# EXS82_USB.net
KiCad netlist of a schematic drawn in Altium Designer
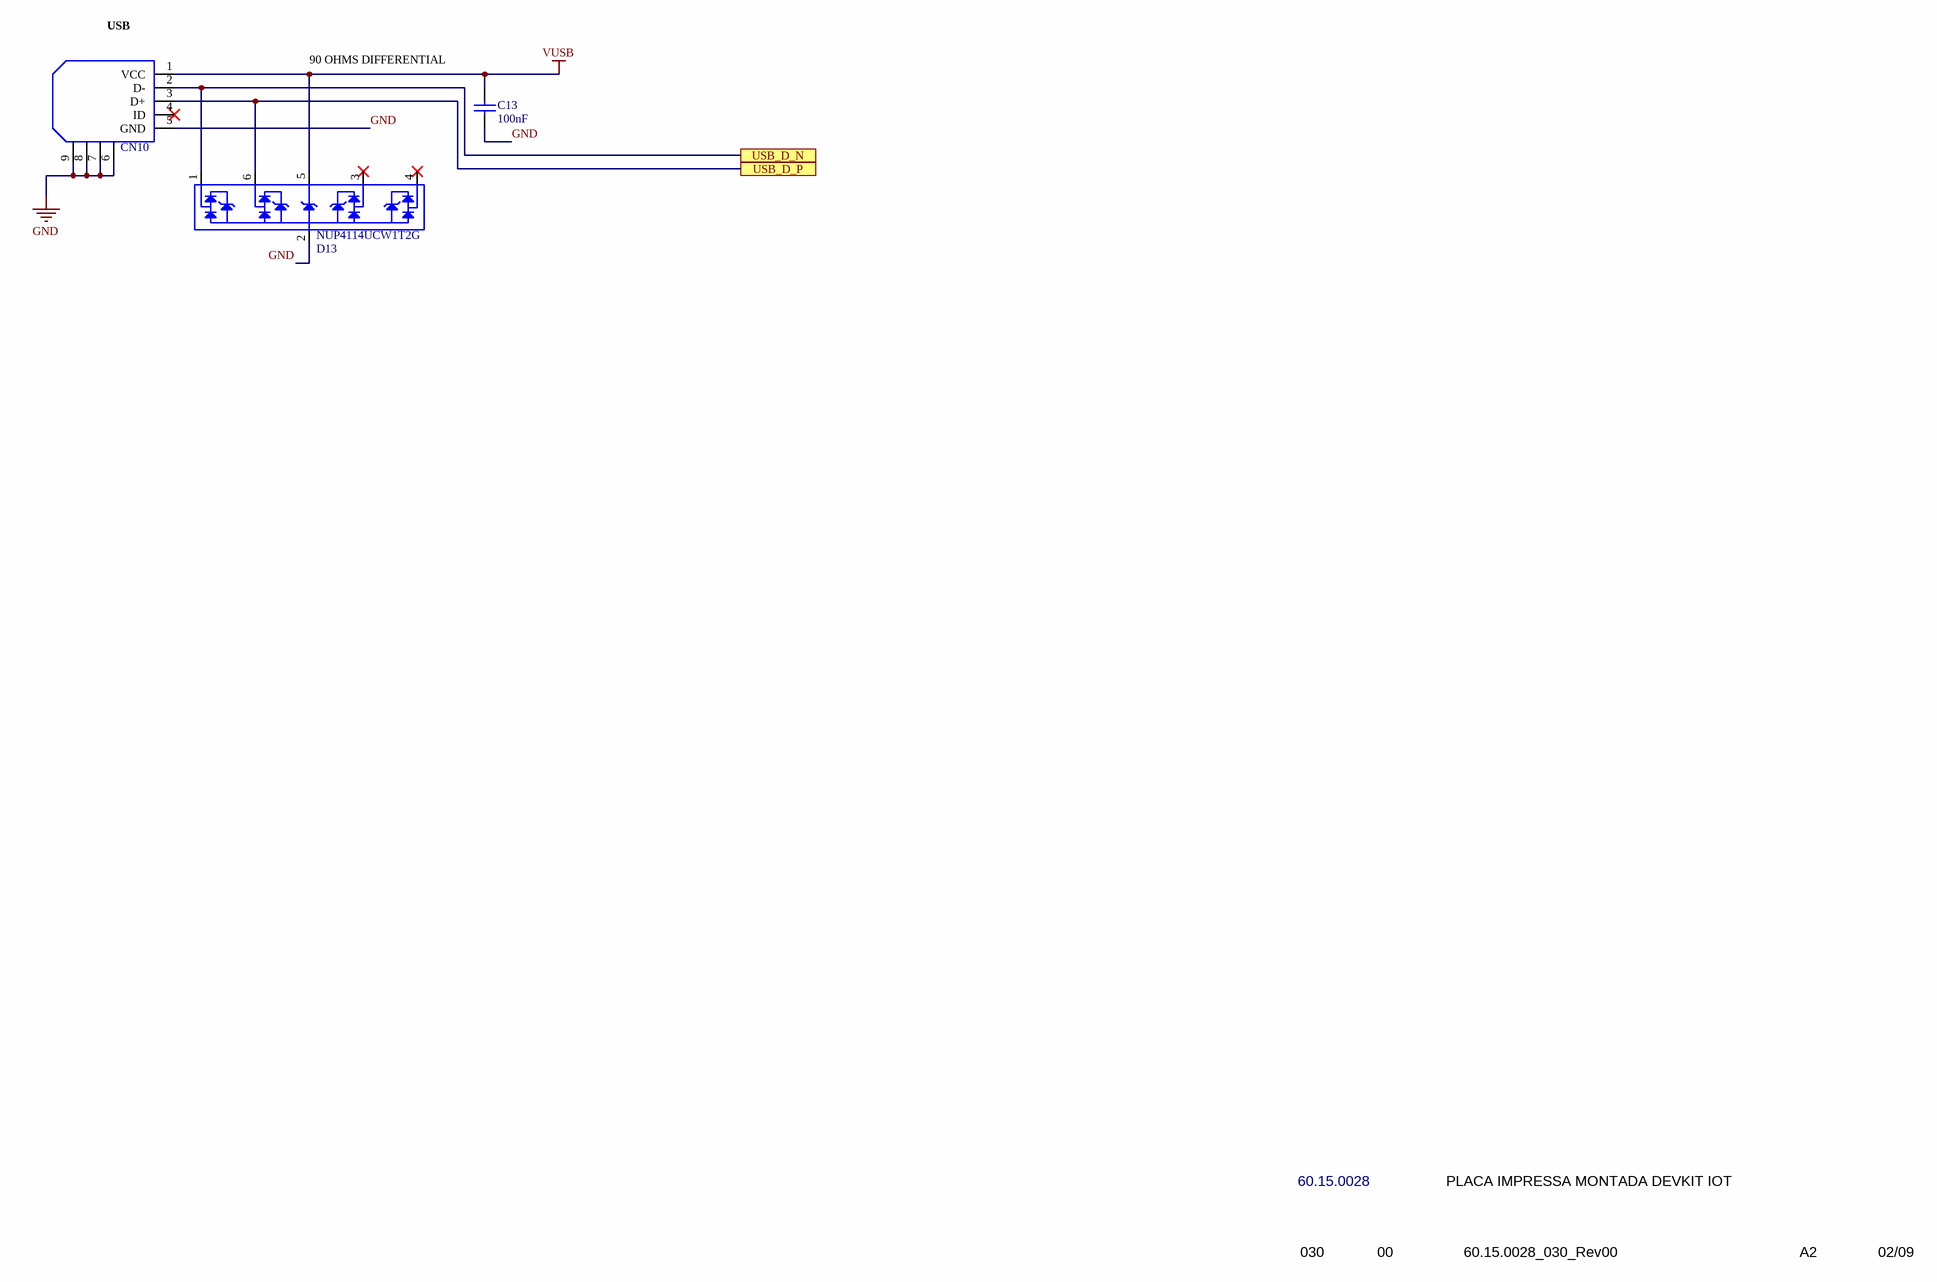
[diagram p0: EXS82_USB.SchDoc]

(export (version "E")
  (design (tool "Eeschema 10.0.6"))
  (components
    (comp (ref "C13")
      (value "16.23.0803")
      (footprint "16.23.0803")
      (description "CAPACITOR CERAMICO 100nF 16V 10%% X5R SMD 0201")
      (fields (field (name "ALTIUM_UNNAMED_1") "100nF"))
      (libsource (lib "OMNI-CAPACITORES") (part "16.23.0803"))
    )
    (comp (ref "CN10")
      (value "28.14.0512")
      (footprint "28.14.0512")
      (description "CONN USB MICRO B RECPT SMT R/A")
      (libsource (lib "OMNI-CONECTORES") (part "28.14.0512"))
    )
    (comp (ref "D13")
      (value "32.27.0043")
      (footprint "32.27.0043")
      (description "DIODO SUPRESSOR 5.5V 10V SC88")
      (fields (field (name "ALTIUM_UNNAMED_1") "NUP4114UCW1T2G"))
      (libsource (lib "OMNI-DIODOS_LED´s_DISPLAYS") (part "32.27.0043"))
    )
  )
  (nets
    (net (code "1") (name "/USB_D_N") (class "Default")
      (node (ref "CN10") (pin "2") (pinfunction "D-_2") (pintype "passive"))
      (node (ref "D13") (pin "1") (pinfunction "1_1") (pintype "passive"))
    )
    (net (code "2") (name "/USB_D_P") (class "Default")
      (node (ref "CN10") (pin "3") (pinfunction "D+_3") (pintype "passive"))
      (node (ref "D13") (pin "6") (pinfunction "6_6") (pintype "passive"))
    )
    (net (code "3") (name "GND") (class "Default")
      (node (ref "C13") (pin "1") (pinfunction "1_1") (pintype "passive"))
      (node (ref "CN10") (pin "5") (pinfunction "GND_5") (pintype "passive"))
      (node (ref "CN10") (pin "6") (pinfunction "SHIELD_6") (pintype "passive"))
      (node (ref "CN10") (pin "7") (pinfunction "SHIELD_7") (pintype "passive"))
      (node (ref "CN10") (pin "8") (pinfunction "SHIELD_8") (pintype "passive"))
      (node (ref "CN10") (pin "9") (pinfunction "SHIELD_9") (pintype "passive"))
      (node (ref "D13") (pin "2") (pinfunction "2_2") (pintype "power_in"))
    )
    (net (code "4") (name "VUSB") (class "Default")
      (node (ref "C13") (pin "2") (pinfunction "2_2") (pintype "passive"))
      (node (ref "CN10") (pin "1") (pinfunction "VCC_1") (pintype "passive"))
      (node (ref "D13") (pin "5") (pinfunction "5_5") (pintype "power_in"))
    )
    (net (code "5") (name "unconnected-(CN10-ID-Pad4)") (class "Default")
      (node (ref "CN10") (pin "4") (pinfunction "ID_4") (pintype "passive+no_connect"))
    )
    (net (code "6") (name "unconnected-(D13-Pad3)") (class "Default")
      (node (ref "D13") (pin "3") (pinfunction "3_3") (pintype "passive+no_connect"))
    )
    (net (code "7") (name "unconnected-(D13-Pad4)") (class "Default")
      (node (ref "D13") (pin "4") (pinfunction "4_4") (pintype "passive+no_connect"))
    )
  )
)
